# main.net
KiCad netlist of a schematic drawn in EAGLE
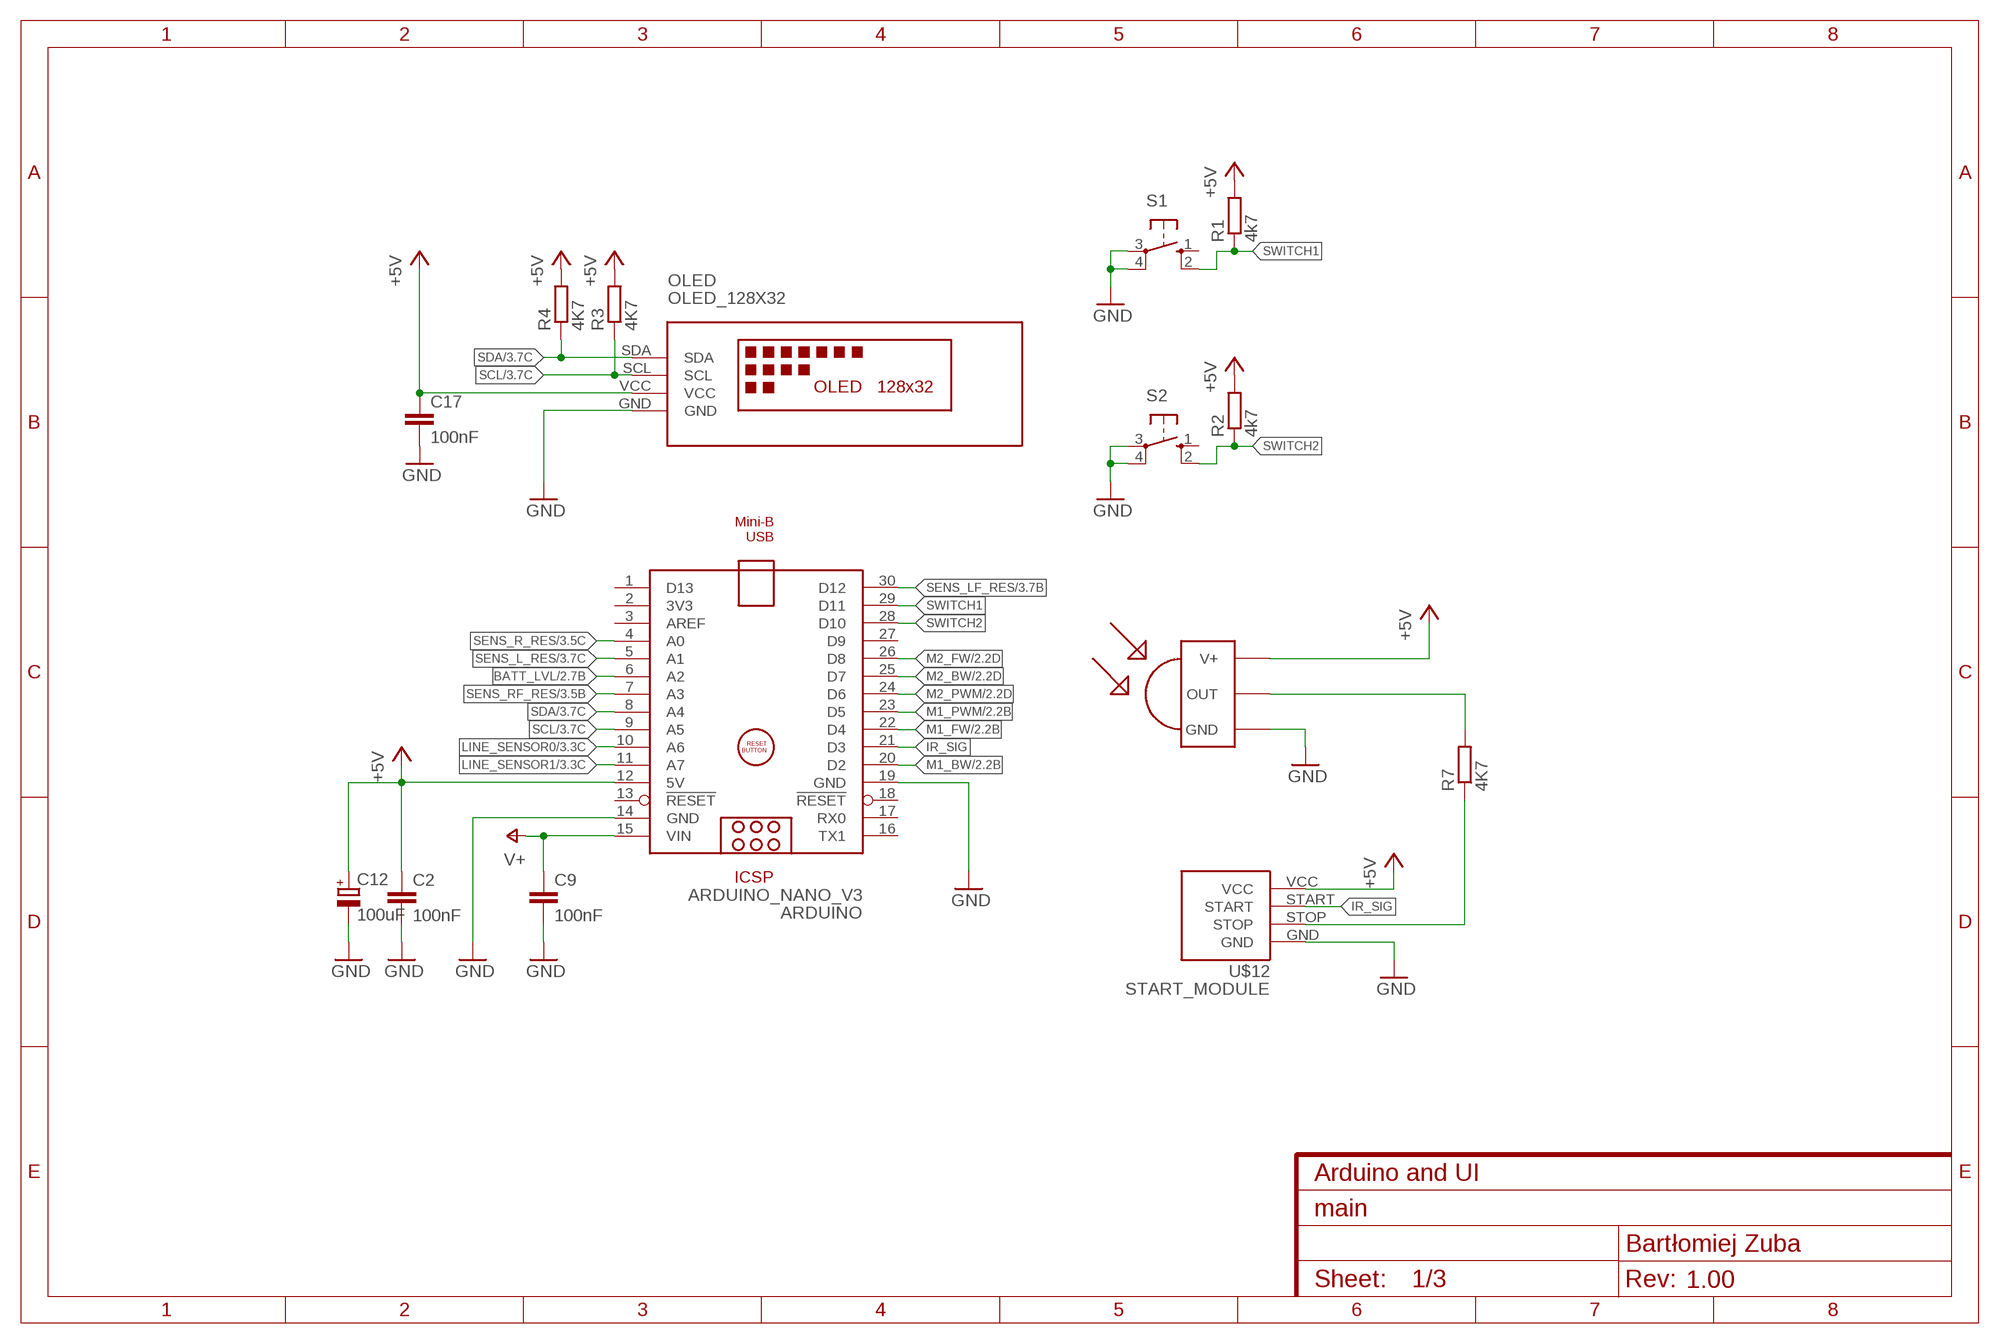
[diagram p0: schematic, sheet 1]
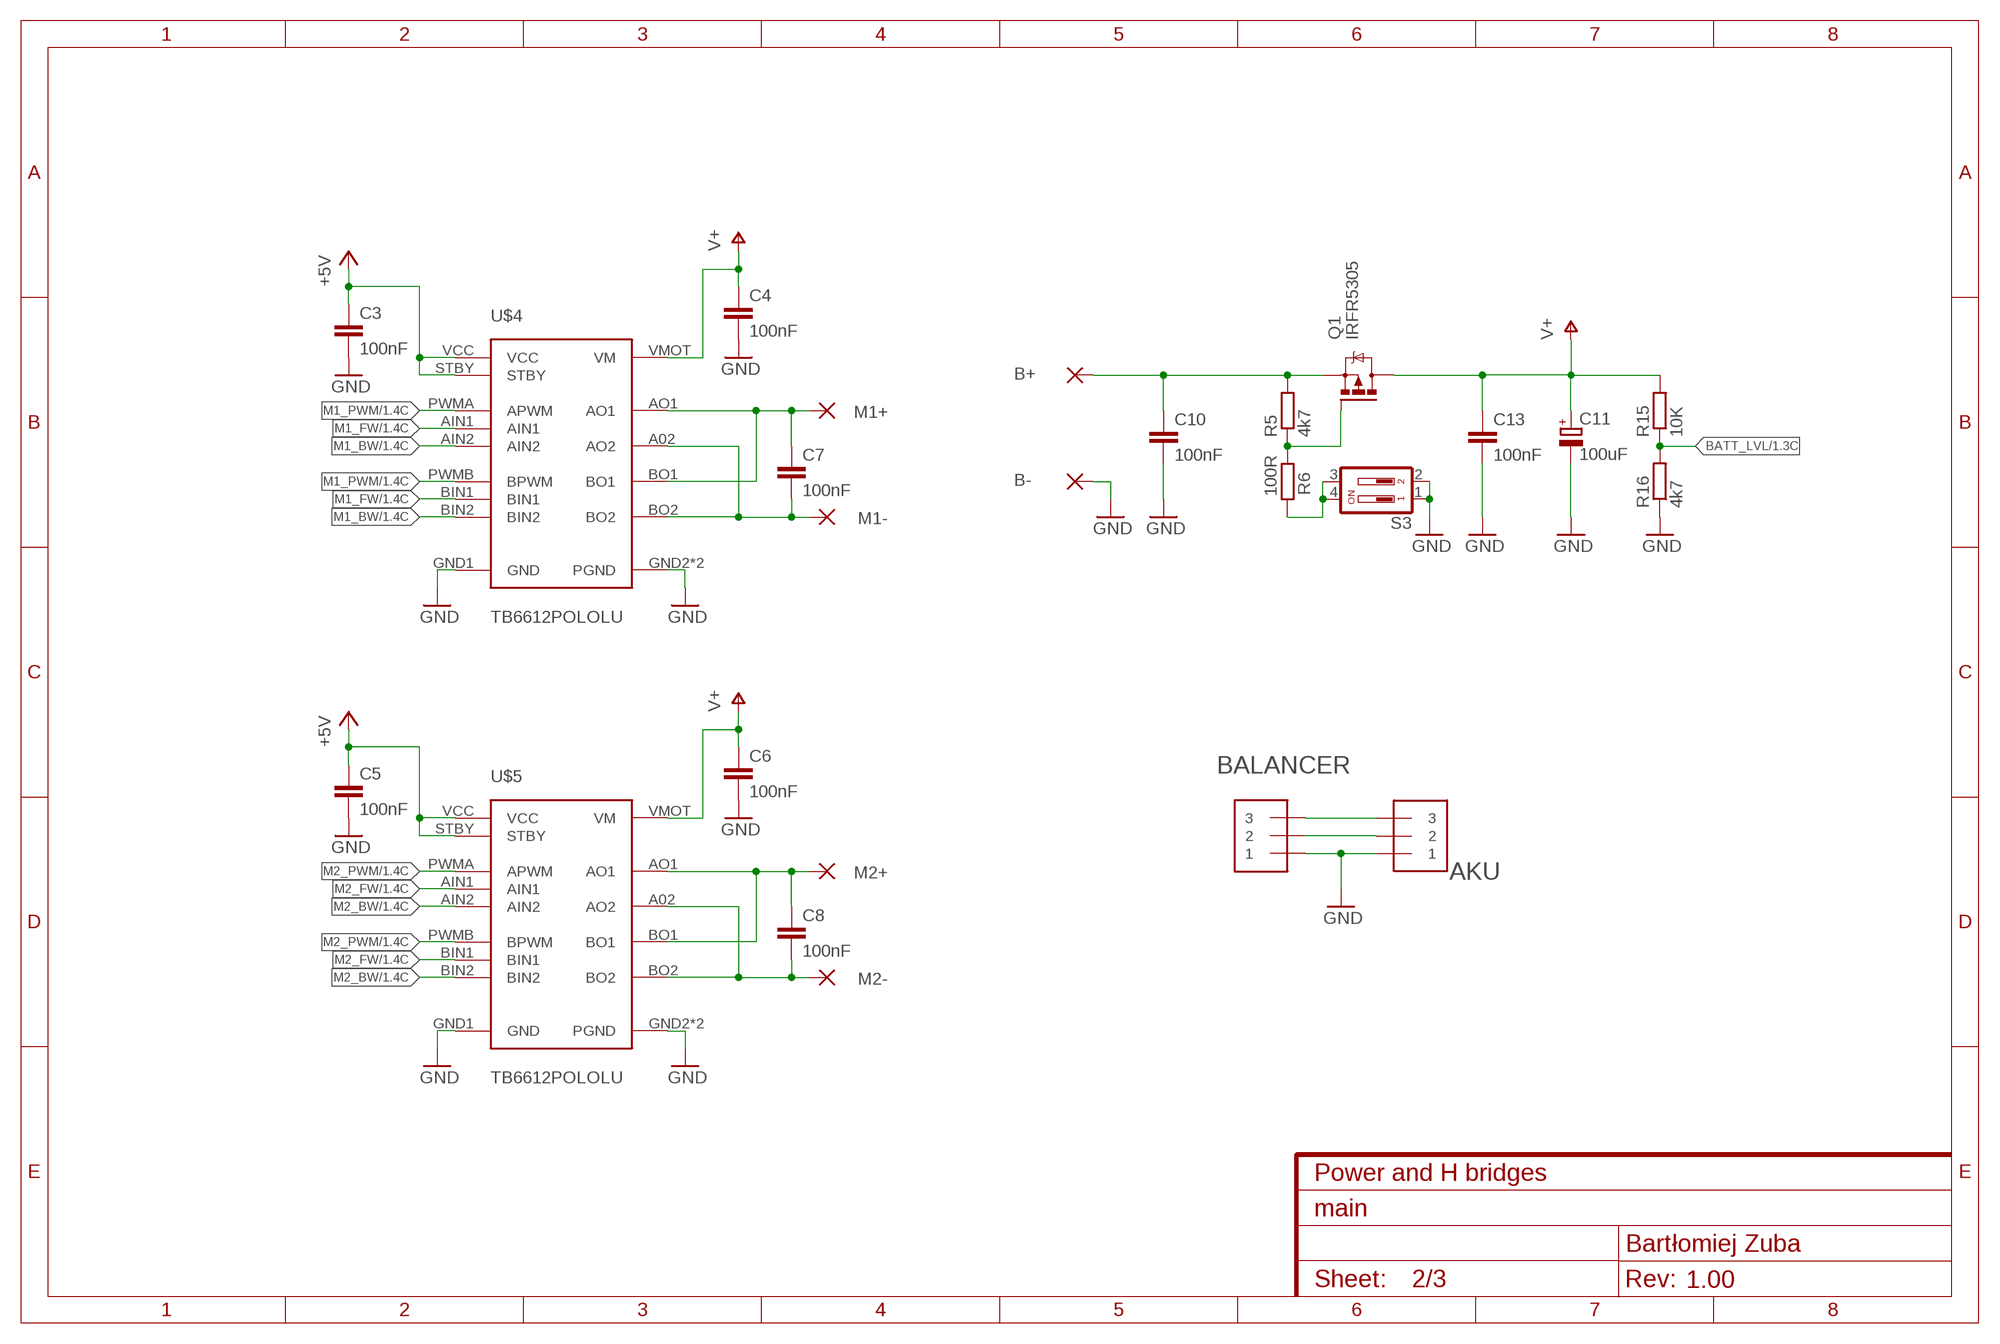
[diagram p1: schematic, sheet 2]
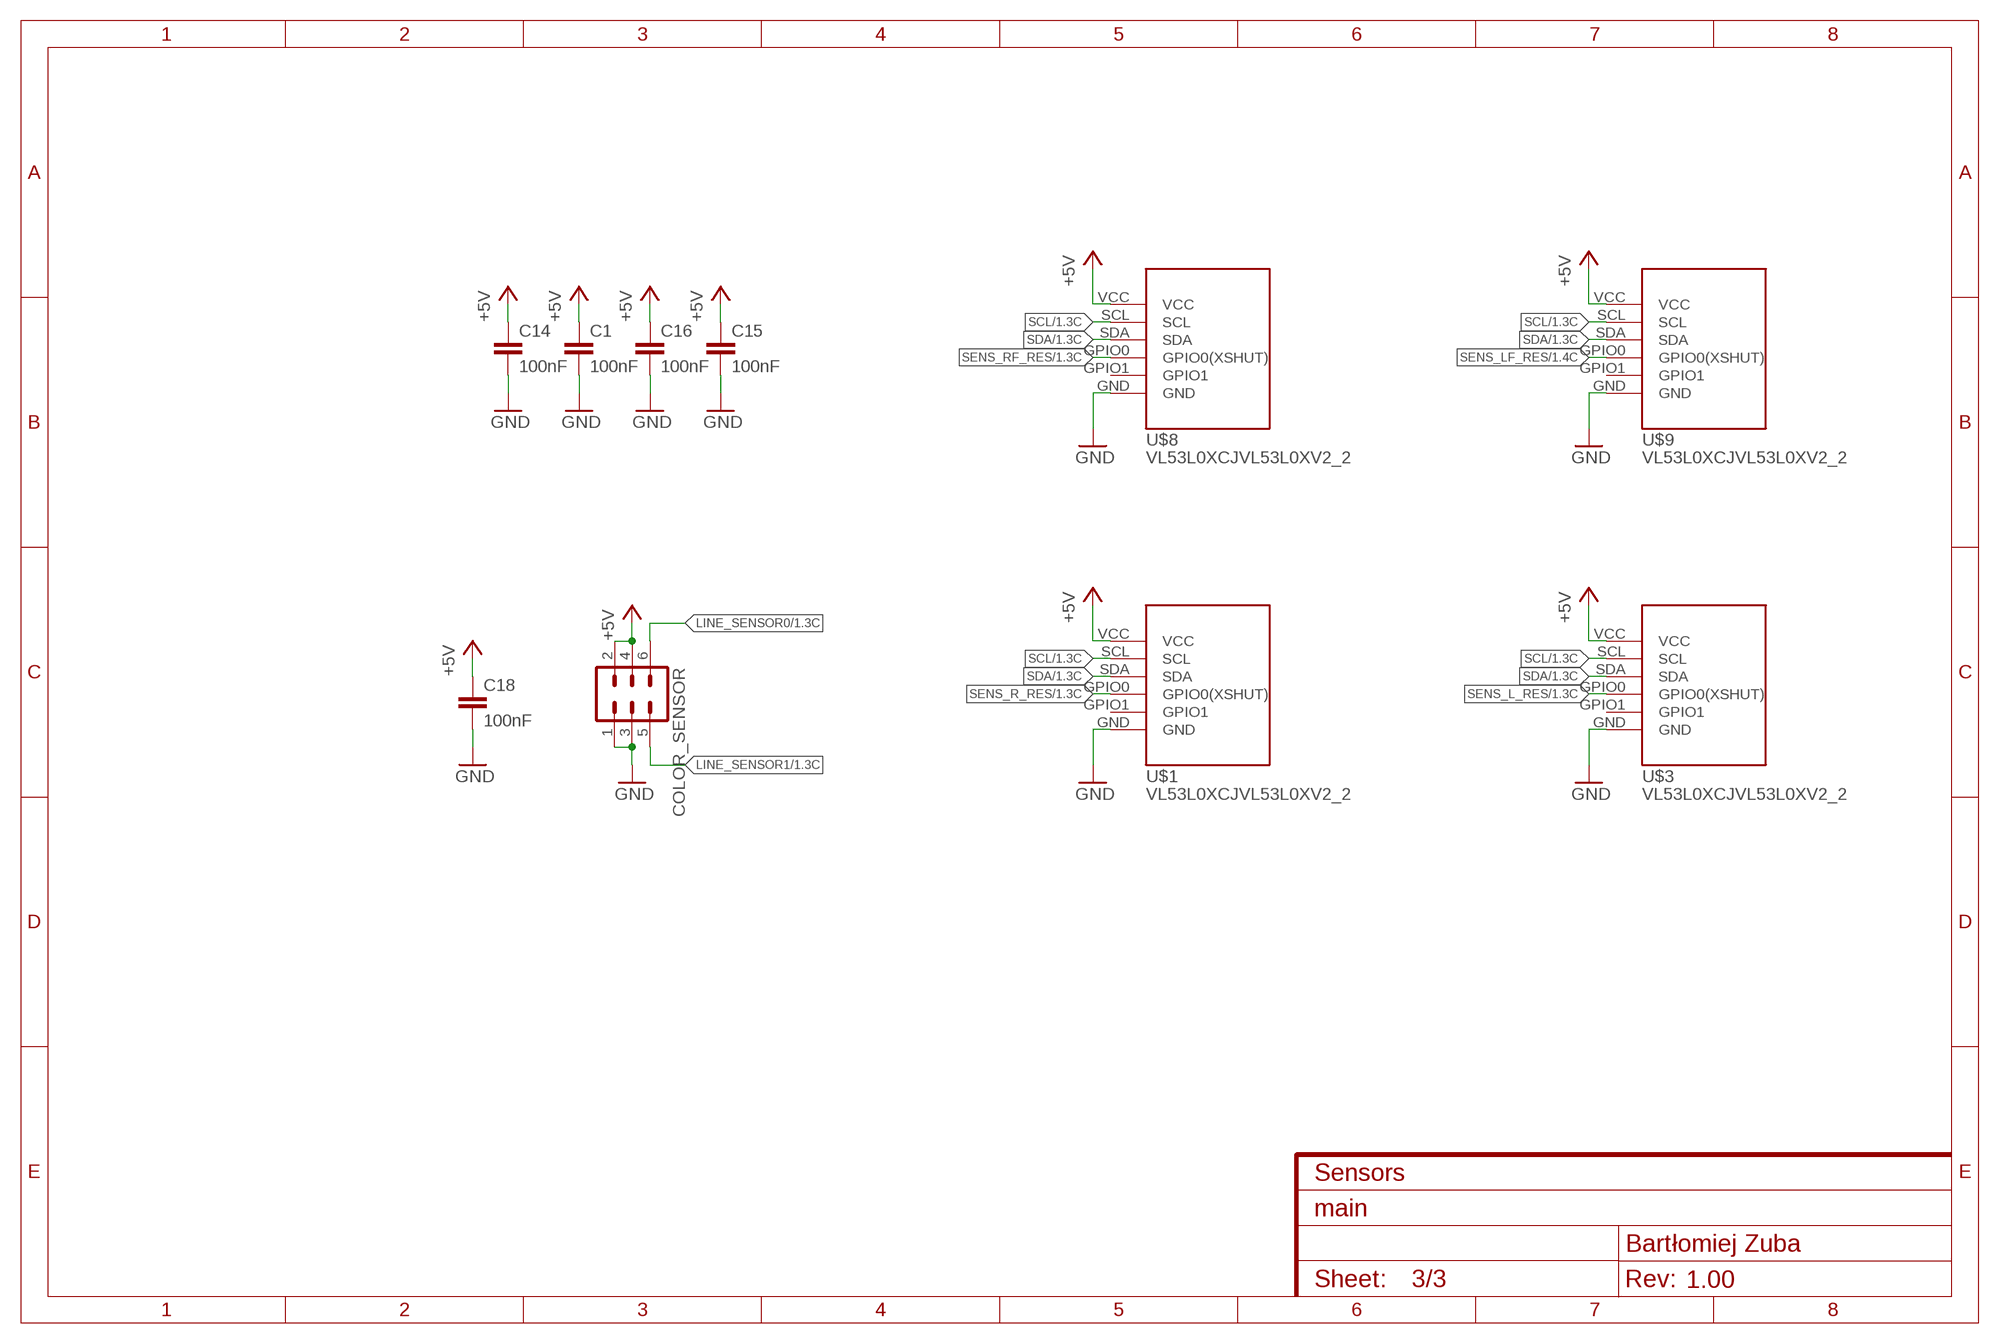
[diagram p2: schematic, sheet 3]

(export (version "E")
  (design (tool "Eeschema 10.0.6"))
  (components
    (comp (ref "AKU")
      (value "JST_ZH_3")
      (footprint "eagle-import:JST_ZH_3")
      (libsource (lib "eagle-import") (part "JST_ZH_3"))
    )
    (comp (ref "B+")
      (value "2,54/1,0")
      (footprint "eagle-import:2,54_1,0")
      (libsource (lib "eagle-import") (part "2,54/1,0"))
    )
    (comp (ref "B-")
      (value "2,54/1,0")
      (footprint "eagle-import:2,54_1,0")
      (libsource (lib "eagle-import") (part "2,54/1,0"))
    )
    (comp (ref "BALANCER")
      (value "JST_ZH_3")
      (footprint "eagle-import:JST_ZH_3")
      (libsource (lib "eagle-import") (part "JST_ZH_3"))
    )
    (comp (ref "C3")
      (value "100nF")
      (footprint "eagle-import:C0805")
      (libsource (lib "eagle-import") (part "C-EUC0805"))
    )
    (comp (ref "C4")
      (value "100nF")
      (footprint "eagle-import:C0805")
      (libsource (lib "eagle-import") (part "C-EUC0805"))
    )
    (comp (ref "C5")
      (value "100nF")
      (footprint "eagle-import:C0805")
      (libsource (lib "eagle-import") (part "C-EUC0805"))
    )
    (comp (ref "C6")
      (value "100nF")
      (footprint "eagle-import:C0805")
      (libsource (lib "eagle-import") (part "C-EUC0805"))
    )
    (comp (ref "C7")
      (value "100nF")
      (footprint "eagle-import:C0805")
      (libsource (lib "eagle-import") (part "C-EUC0805"))
    )
    (comp (ref "C8")
      (value "100nF")
      (footprint "eagle-import:C0805")
      (libsource (lib "eagle-import") (part "C-EUC0805"))
    )
    (comp (ref "C10")
      (value "100nF")
      (footprint "eagle-import:C0805")
      (libsource (lib "eagle-import") (part "C-EUC0805"))
    )
    (comp (ref "C11")
      (value "100uF")
      (footprint "eagle-import:E3,5-8")
      (libsource (lib "eagle-import") (part "CPOL-EUE3.5-8"))
    )
    (comp (ref "C13")
      (value "100nF")
      (footprint "eagle-import:C0805")
      (libsource (lib "eagle-import") (part "C-EUC0805"))
    )
    (comp (ref "M1+")
      (value "2,54/1,0")
      (footprint "eagle-import:2,54_1,0")
      (libsource (lib "eagle-import") (part "2,54/1,0"))
    )
    (comp (ref "M1-")
      (value "2,54/1,0")
      (footprint "eagle-import:2,54_1,0")
      (libsource (lib "eagle-import") (part "2,54/1,0"))
    )
    (comp (ref "M2+")
      (value "2,54/1,0")
      (footprint "eagle-import:2,54_1,0")
      (libsource (lib "eagle-import") (part "2,54/1,0"))
    )
    (comp (ref "M2-")
      (value "2,54/1,0")
      (footprint "eagle-import:2,54_1,0")
      (libsource (lib "eagle-import") (part "2,54/1,0"))
    )
    (comp (ref "Q1")
      (value "IRFR5305")
      (footprint "eagle-import:D-PAK_TO252AA")
      (libsource (lib "eagle-import") (part "IRF?5305R"))
    )
    (comp (ref "R5")
      (value "4k7")
      (footprint "eagle-import:M0805")
      (libsource (lib "eagle-import") (part "R-EU_M0805"))
    )
    (comp (ref "R6")
      (value "100R")
      (footprint "eagle-import:M0805")
      (libsource (lib "eagle-import") (part "R-EU_M0805"))
    )
    (comp (ref "R15")
      (value "10K")
      (footprint "eagle-import:M0805")
      (libsource (lib "eagle-import") (part "R-EU_M0805"))
    )
    (comp (ref "R16")
      (value "4k7")
      (footprint "eagle-import:M0805")
      (libsource (lib "eagle-import") (part "R-EU_M0805"))
    )
    (comp (ref "S3")
      (value "DS02")
      (footprint "eagle-import:DS-02")
      (libsource (lib "eagle-import") (part "DS02"))
    )
    (comp (ref "U$4")
      (value "TB6612POLOLU")
      (footprint "eagle-import:POLOLU")
      (libsource (lib "eagle-import") (part "TB6612POLOLU"))
    )
    (comp (ref "U$5")
      (value "TB6612POLOLU")
      (footprint "eagle-import:POLOLU")
      (libsource (lib "eagle-import") (part "TB6612POLOLU"))
    )
    (comp (ref "ARDUINO")
      (value "ARDUINO_NANO_V3")
      (footprint "eagle-import:ARDUINO_NANO_V3")
      (libsource (lib "eagle-import") (part "ARDUINO_NANO_V3"))
    )
    (comp (ref "C2")
      (value "100nF")
      (footprint "eagle-import:C0805")
      (libsource (lib "eagle-import") (part "C-EUC0805"))
    )
    (comp (ref "C9")
      (value "100nF")
      (footprint "eagle-import:C0805")
      (libsource (lib "eagle-import") (part "C-EUC0805"))
    )
    (comp (ref "C12")
      (value "100uF")
      (footprint "eagle-import:E3,5-8")
      (libsource (lib "eagle-import") (part "CPOL-EUE3.5-8"))
    )
    (comp (ref "C17")
      (value "100nF")
      (footprint "eagle-import:C0805")
      (libsource (lib "eagle-import") (part "C-EUC0805"))
    )
    (comp (ref "OLED")
      (value "OLED_128X32")
      (footprint "eagle-import:OLED")
      (libsource (lib "eagle-import") (part "OLED_128X32"))
    )
    (comp (ref "R1")
      (value "4k7")
      (footprint "eagle-import:M0805")
      (libsource (lib "eagle-import") (part "R-EU_M0805"))
    )
    (comp (ref "R2")
      (value "4k7")
      (footprint "eagle-import:M0805")
      (libsource (lib "eagle-import") (part "R-EU_M0805"))
    )
    (comp (ref "R3")
      (value "4K7")
      (footprint "eagle-import:M0805")
      (libsource (lib "eagle-import") (part "R-EU_M0805"))
    )
    (comp (ref "R4")
      (value "4K7")
      (footprint "eagle-import:M0805")
      (libsource (lib "eagle-import") (part "R-EU_M0805"))
    )
    (comp (ref "R7")
      (value "4K7")
      (footprint "eagle-import:M0805")
      (libsource (lib "eagle-import") (part "R-EU_M0805"))
    )
    (comp (ref "S1")
      (value "10-XX")
      (footprint "eagle-import:B3F-10XX")
      (fields (field (name "MPN") "B3F-1000"))
      (libsource (lib "eagle-import") (part "10-XX"))
    )
    (comp (ref "S2")
      (value "10-XX")
      (footprint "eagle-import:B3F-10XX")
      (fields (field (name "MPN") "B3F-1000"))
      (libsource (lib "eagle-import") (part "10-XX"))
    )
    (comp (ref "U$2")
      (value "TSOP4838")
      (footprint "eagle-import:TSOP")
      (libsource (lib "eagle-import") (part "TSOP4838"))
    )
    (comp (ref "U$12")
      (value "START_MODULE")
      (footprint "eagle-import:START_MODULE")
      (libsource (lib "eagle-import") (part "START_MODULE"))
    )
    (comp (ref "C1")
      (value "100nF")
      (footprint "eagle-import:C0805")
      (libsource (lib "eagle-import") (part "C-EUC0805"))
    )
    (comp (ref "C14")
      (value "100nF")
      (footprint "eagle-import:C0805")
      (libsource (lib "eagle-import") (part "C-EUC0805"))
    )
    (comp (ref "C15")
      (value "100nF")
      (footprint "eagle-import:C0805")
      (libsource (lib "eagle-import") (part "C-EUC0805"))
    )
    (comp (ref "C16")
      (value "100nF")
      (footprint "eagle-import:C0805")
      (libsource (lib "eagle-import") (part "C-EUC0805"))
    )
    (comp (ref "C18")
      (value "100nF")
      (footprint "eagle-import:C0805")
      (libsource (lib "eagle-import") (part "C-EUC0805"))
    )
    (comp (ref "COLOR_SENSOR")
      (value "MA03-2")
      (footprint "eagle-import:MA03-2")
      (libsource (lib "eagle-import") (part "MA03-2"))
    )
    (comp (ref "U$1")
      (value "VL53L0XCJVL53L0XV2_2")
      (footprint "eagle-import:VL53L0X_4")
      (libsource (lib "eagle-import") (part "VL53L0XCJVL53L0XV2_2"))
    )
    (comp (ref "U$3")
      (value "VL53L0XCJVL53L0XV2_2")
      (footprint "eagle-import:VL53L0X_4")
      (libsource (lib "eagle-import") (part "VL53L0XCJVL53L0XV2_2"))
    )
    (comp (ref "U$8")
      (value "VL53L0XCJVL53L0XV2_2")
      (footprint "eagle-import:VL53L0X_4")
      (libsource (lib "eagle-import") (part "VL53L0XCJVL53L0XV2_2"))
    )
    (comp (ref "U$9")
      (value "VL53L0XCJVL53L0XV2_2")
      (footprint "eagle-import:VL53L0X_4")
      (libsource (lib "eagle-import") (part "VL53L0XCJVL53L0XV2_2"))
    )
  )
  (nets
    (net (code "1") (name "+5V") (class "Default")
      (node (ref "ARDUINO") (pin "12") (pinfunction "5V_12") (pintype "power_in"))
      (node (ref "C1") (pin "1") (pinfunction "1_1") (pintype "passive"))
      (node (ref "C12") (pin "+") (pinfunction "+_+") (pintype "passive"))
      (node (ref "C14") (pin "1") (pinfunction "1_1") (pintype "passive"))
      (node (ref "C15") (pin "1") (pinfunction "1_1") (pintype "passive"))
      (node (ref "C16") (pin "1") (pinfunction "1_1") (pintype "passive"))
      (node (ref "C17") (pin "1") (pinfunction "1_1") (pintype "passive"))
      (node (ref "C18") (pin "1") (pinfunction "1_1") (pintype "passive"))
      (node (ref "C2") (pin "1") (pinfunction "1_1") (pintype "passive"))
      (node (ref "C3") (pin "1") (pinfunction "1_1") (pintype "passive"))
      (node (ref "C5") (pin "1") (pinfunction "1_1") (pintype "passive"))
      (node (ref "COLOR_SENSOR") (pin "2") (pinfunction "2_2") (pintype "passive"))
      (node (ref "COLOR_SENSOR") (pin "4") (pinfunction "4_4") (pintype "passive"))
      (node (ref "OLED") (pin "VCC") (pinfunction "VCC_VCC") (pintype "power_in"))
      (node (ref "R1") (pin "2") (pinfunction "2_2") (pintype "passive"))
      (node (ref "R2") (pin "2") (pinfunction "2_2") (pintype "passive"))
      (node (ref "R3") (pin "2") (pinfunction "2_2") (pintype "passive"))
      (node (ref "R4") (pin "2") (pinfunction "2_2") (pintype "passive"))
      (node (ref "U$1") (pin "VCC") (pinfunction "VCC_VCC") (pintype "bidirectional"))
      (node (ref "U$12") (pin "VCC") (pinfunction "VCC_VCC") (pintype "bidirectional"))
      (node (ref "U$2") (pin "VCC") (pinfunction "V+_VCC") (pintype "bidirectional"))
      (node (ref "U$3") (pin "VCC") (pinfunction "VCC_VCC") (pintype "bidirectional"))
      (node (ref "U$4") (pin "STBY") (pinfunction "STBY_STBY") (pintype "bidirectional"))
      (node (ref "U$4") (pin "VCC") (pinfunction "VCC_VCC") (pintype "bidirectional"))
      (node (ref "U$5") (pin "STBY") (pinfunction "STBY_STBY") (pintype "bidirectional"))
      (node (ref "U$5") (pin "VCC") (pinfunction "VCC_VCC") (pintype "bidirectional"))
      (node (ref "U$8") (pin "VCC") (pinfunction "VCC_VCC") (pintype "bidirectional"))
      (node (ref "U$9") (pin "VCC") (pinfunction "VCC_VCC") (pintype "bidirectional"))
    )
    (net (code "2") (name "BATT_LVL") (class "Default")
      (node (ref "ARDUINO") (pin "6") (pinfunction "A2_6") (pintype "bidirectional"))
      (node (ref "R15") (pin "1") (pinfunction "1_1") (pintype "passive"))
      (node (ref "R16") (pin "2") (pinfunction "2_2") (pintype "passive"))
    )
    (net (code "3") (name "GND") (class "Default")
      (node (ref "AKU") (pin "P$1") (pinfunction "1_P$1") (pintype "bidirectional"))
      (node (ref "ARDUINO") (pin "14") (pinfunction "GND_14") (pintype "power_in"))
      (node (ref "ARDUINO") (pin "19") (pinfunction "GND_19") (pintype "power_in"))
      (node (ref "B-") (pin "1") (pinfunction "P_1") (pintype "passive"))
      (node (ref "BALANCER") (pin "P$1") (pinfunction "1_P$1") (pintype "bidirectional"))
      (node (ref "C1") (pin "2") (pinfunction "2_2") (pintype "passive"))
      (node (ref "C10") (pin "2") (pinfunction "2_2") (pintype "passive"))
      (node (ref "C11") (pin "-") (pinfunction "-_-") (pintype "passive"))
      (node (ref "C12") (pin "-") (pinfunction "-_-") (pintype "passive"))
      (node (ref "C13") (pin "2") (pinfunction "2_2") (pintype "passive"))
      (node (ref "C14") (pin "2") (pinfunction "2_2") (pintype "passive"))
      (node (ref "C15") (pin "2") (pinfunction "2_2") (pintype "passive"))
      (node (ref "C16") (pin "2") (pinfunction "2_2") (pintype "passive"))
      (node (ref "C17") (pin "2") (pinfunction "2_2") (pintype "passive"))
      (node (ref "C18") (pin "2") (pinfunction "2_2") (pintype "passive"))
      (node (ref "C2") (pin "2") (pinfunction "2_2") (pintype "passive"))
      (node (ref "C3") (pin "2") (pinfunction "2_2") (pintype "passive"))
      (node (ref "C4") (pin "2") (pinfunction "2_2") (pintype "passive"))
      (node (ref "C5") (pin "2") (pinfunction "2_2") (pintype "passive"))
      (node (ref "C6") (pin "2") (pinfunction "2_2") (pintype "passive"))
      (node (ref "C9") (pin "2") (pinfunction "2_2") (pintype "passive"))
      (node (ref "COLOR_SENSOR") (pin "1") (pinfunction "1_1") (pintype "passive"))
      (node (ref "COLOR_SENSOR") (pin "3") (pinfunction "3_3") (pintype "passive"))
      (node (ref "OLED") (pin "GND") (pinfunction "GND_GND") (pintype "power_in"))
      (node (ref "R16") (pin "1") (pinfunction "1_1") (pintype "passive"))
      (node (ref "S1") (pin "3") (pinfunction "P_3") (pintype "passive"))
      (node (ref "S1") (pin "4") (pinfunction "P1_4") (pintype "passive"))
      (node (ref "S2") (pin "3") (pinfunction "P_3") (pintype "passive"))
      (node (ref "S2") (pin "4") (pinfunction "P1_4") (pintype "passive"))
      (node (ref "S3") (pin "1") (pinfunction "1_1") (pintype "passive"))
      (node (ref "S3") (pin "2") (pinfunction "2_2") (pintype "passive"))
      (node (ref "U$1") (pin "GND") (pinfunction "GND_GND") (pintype "bidirectional"))
      (node (ref "U$12") (pin "GND") (pinfunction "GND_GND") (pintype "bidirectional"))
      (node (ref "U$2") (pin "GND") (pinfunction "GND_GND") (pintype "bidirectional"))
      (node (ref "U$3") (pin "GND") (pinfunction "GND_GND") (pintype "bidirectional"))
      (node (ref "U$4") (pin "GND1") (pinfunction "GND_GND1") (pintype "bidirectional"))
      (node (ref "U$4") (pin "GND2") (pinfunction "PGND_GND2") (pintype "bidirectional"))
      (node (ref "U$4") (pin "GND3") (pinfunction "PGND_GND3") (pintype "bidirectional"))
      (node (ref "U$5") (pin "GND1") (pinfunction "GND_GND1") (pintype "bidirectional"))
      (node (ref "U$5") (pin "GND2") (pinfunction "PGND_GND2") (pintype "bidirectional"))
      (node (ref "U$5") (pin "GND3") (pinfunction "PGND_GND3") (pintype "bidirectional"))
      (node (ref "U$8") (pin "GND") (pinfunction "GND_GND") (pintype "bidirectional"))
      (node (ref "U$9") (pin "GND") (pinfunction "GND_GND") (pintype "bidirectional"))
    )
    (net (code "4") (name "IR_SIG") (class "Default")
      (node (ref "ARDUINO") (pin "21") (pinfunction "D3_21") (pintype "bidirectional"))
      (node (ref "U$12") (pin "START") (pinfunction "START_START") (pintype "bidirectional"))
    )
    (net (code "5") (name "LINE_SENSOR0") (class "Default")
      (node (ref "ARDUINO") (pin "10") (pinfunction "A6_10") (pintype "bidirectional"))
      (node (ref "COLOR_SENSOR") (pin "6") (pinfunction "6_6") (pintype "passive"))
    )
    (net (code "6") (name "LINE_SENSOR1") (class "Default")
      (node (ref "ARDUINO") (pin "11") (pinfunction "A7_11") (pintype "bidirectional"))
      (node (ref "COLOR_SENSOR") (pin "5") (pinfunction "5_5") (pintype "passive"))
    )
    (net (code "7") (name "M1_BW") (class "Default")
      (node (ref "ARDUINO") (pin "20") (pinfunction "D2_20") (pintype "bidirectional"))
      (node (ref "U$4") (pin "AIN2") (pinfunction "AIN2_AIN2") (pintype "bidirectional"))
      (node (ref "U$4") (pin "BIN2") (pinfunction "BIN2_BIN2") (pintype "bidirectional"))
    )
    (net (code "8") (name "M1_FW") (class "Default")
      (node (ref "ARDUINO") (pin "22") (pinfunction "D4_22") (pintype "bidirectional"))
      (node (ref "U$4") (pin "AIN1") (pinfunction "AIN1_AIN1") (pintype "bidirectional"))
      (node (ref "U$4") (pin "BIN1") (pinfunction "BIN1_BIN1") (pintype "bidirectional"))
    )
    (net (code "9") (name "M1_PWM") (class "Default")
      (node (ref "ARDUINO") (pin "23") (pinfunction "D5_23") (pintype "bidirectional"))
      (node (ref "U$4") (pin "PWMA") (pinfunction "APWM_PWMA") (pintype "bidirectional"))
      (node (ref "U$4") (pin "PWMB") (pinfunction "BPWM_PWMB") (pintype "bidirectional"))
    )
    (net (code "10") (name "M2_BW") (class "Default")
      (node (ref "ARDUINO") (pin "25") (pinfunction "D7_25") (pintype "bidirectional"))
      (node (ref "U$5") (pin "AIN2") (pinfunction "AIN2_AIN2") (pintype "bidirectional"))
      (node (ref "U$5") (pin "BIN2") (pinfunction "BIN2_BIN2") (pintype "bidirectional"))
    )
    (net (code "11") (name "M2_FW") (class "Default")
      (node (ref "ARDUINO") (pin "26") (pinfunction "D8_26") (pintype "bidirectional"))
      (node (ref "U$5") (pin "AIN1") (pinfunction "AIN1_AIN1") (pintype "bidirectional"))
      (node (ref "U$5") (pin "BIN1") (pinfunction "BIN1_BIN1") (pintype "bidirectional"))
    )
    (net (code "12") (name "M2_PWM") (class "Default")
      (node (ref "ARDUINO") (pin "24") (pinfunction "D6_24") (pintype "bidirectional"))
      (node (ref "U$5") (pin "PWMA") (pinfunction "APWM_PWMA") (pintype "bidirectional"))
      (node (ref "U$5") (pin "PWMB") (pinfunction "BPWM_PWMB") (pintype "bidirectional"))
    )
    (net (code "13") (name "Net-(AKU-2)") (class "Default")
      (node (ref "AKU") (pin "P$2") (pinfunction "2_P$2") (pintype "bidirectional"))
      (node (ref "BALANCER") (pin "P$2") (pinfunction "2_P$2") (pintype "bidirectional"))
    )
    (net (code "14") (name "Net-(AKU-3)") (class "Default")
      (node (ref "AKU") (pin "P$3") (pinfunction "3_P$3") (pintype "bidirectional"))
      (node (ref "BALANCER") (pin "P$3") (pinfunction "3_P$3") (pintype "bidirectional"))
    )
    (net (code "15") (name "Net-(B+-P)") (class "Default")
      (node (ref "B+") (pin "1") (pinfunction "P_1") (pintype "passive"))
      (node (ref "C10") (pin "1") (pinfunction "1_1") (pintype "passive"))
      (node (ref "Q1") (pin "3") (pinfunction "S_3") (pintype "passive"))
      (node (ref "R5") (pin "2") (pinfunction "2_2") (pintype "passive"))
    )
    (net (code "16") (name "Net-(M1+-P)") (class "Default")
      (node (ref "C7") (pin "1") (pinfunction "1_1") (pintype "passive"))
      (node (ref "M1+") (pin "1") (pinfunction "P_1") (pintype "passive"))
      (node (ref "U$4") (pin "AO1") (pinfunction "AO1_AO1") (pintype "bidirectional"))
      (node (ref "U$4") (pin "BO1") (pinfunction "BO1_BO1") (pintype "bidirectional"))
    )
    (net (code "17") (name "Net-(M1--P)") (class "Default")
      (node (ref "C7") (pin "2") (pinfunction "2_2") (pintype "passive"))
      (node (ref "M1-") (pin "1") (pinfunction "P_1") (pintype "passive"))
      (node (ref "U$4") (pin "A02") (pinfunction "AO2_A02") (pintype "bidirectional"))
      (node (ref "U$4") (pin "BO2") (pinfunction "BO2_BO2") (pintype "bidirectional"))
    )
    (net (code "18") (name "Net-(M2+-P)") (class "Default")
      (node (ref "C8") (pin "1") (pinfunction "1_1") (pintype "passive"))
      (node (ref "M2+") (pin "1") (pinfunction "P_1") (pintype "passive"))
      (node (ref "U$5") (pin "AO1") (pinfunction "AO1_AO1") (pintype "bidirectional"))
      (node (ref "U$5") (pin "BO1") (pinfunction "BO1_BO1") (pintype "bidirectional"))
    )
    (net (code "19") (name "Net-(M2--P)") (class "Default")
      (node (ref "C8") (pin "2") (pinfunction "2_2") (pintype "passive"))
      (node (ref "M2-") (pin "1") (pinfunction "P_1") (pintype "passive"))
      (node (ref "U$5") (pin "A02") (pinfunction "AO2_A02") (pintype "bidirectional"))
      (node (ref "U$5") (pin "BO2") (pinfunction "BO2_BO2") (pintype "bidirectional"))
    )
    (net (code "20") (name "Net-(Q1-G)") (class "Default")
      (node (ref "Q1") (pin "1") (pinfunction "G_1") (pintype "passive"))
      (node (ref "R5") (pin "1") (pinfunction "1_1") (pintype "passive"))
      (node (ref "R6") (pin "1") (pinfunction "1_1") (pintype "passive"))
    )
    (net (code "21") (name "Net-(R6-Pad2)") (class "Default")
      (node (ref "R6") (pin "2") (pinfunction "2_2") (pintype "passive"))
      (node (ref "S3") (pin "3") (pinfunction "3_3") (pintype "passive"))
      (node (ref "S3") (pin "4") (pinfunction "4_4") (pintype "passive"))
    )
    (net (code "22") (name "Net-(R7-Pad1)") (class "Default")
      (node (ref "R7") (pin "1") (pinfunction "1_1") (pintype "passive"))
      (node (ref "U$12") (pin "STOP") (pinfunction "STOP_STOP") (pintype "bidirectional"))
    )
    (net (code "23") (name "Net-(R7-Pad2)") (class "Default")
      (node (ref "R7") (pin "2") (pinfunction "2_2") (pintype "passive"))
      (node (ref "U$2") (pin "OUT") (pinfunction "OUT_OUT") (pintype "bidirectional"))
    )
    (net (code "24") (name "SCL") (class "Default")
      (node (ref "ARDUINO") (pin "9") (pinfunction "A5_9") (pintype "bidirectional"))
      (node (ref "OLED") (pin "SCL") (pinfunction "SCL_SCL") (pintype "bidirectional"))
      (node (ref "R3") (pin "1") (pinfunction "1_1") (pintype "passive"))
      (node (ref "U$1") (pin "SCL") (pinfunction "SCL_SCL") (pintype "bidirectional"))
      (node (ref "U$3") (pin "SCL") (pinfunction "SCL_SCL") (pintype "bidirectional"))
      (node (ref "U$8") (pin "SCL") (pinfunction "SCL_SCL") (pintype "bidirectional"))
      (node (ref "U$9") (pin "SCL") (pinfunction "SCL_SCL") (pintype "bidirectional"))
    )
    (net (code "25") (name "SDA") (class "Default")
      (node (ref "ARDUINO") (pin "8") (pinfunction "A4_8") (pintype "bidirectional"))
      (node (ref "OLED") (pin "SDA") (pinfunction "SDA_SDA") (pintype "bidirectional"))
      (node (ref "R4") (pin "1") (pinfunction "1_1") (pintype "passive"))
      (node (ref "U$1") (pin "SDA") (pinfunction "SDA_SDA") (pintype "bidirectional"))
      (node (ref "U$3") (pin "SDA") (pinfunction "SDA_SDA") (pintype "bidirectional"))
      (node (ref "U$8") (pin "SDA") (pinfunction "SDA_SDA") (pintype "bidirectional"))
      (node (ref "U$9") (pin "SDA") (pinfunction "SDA_SDA") (pintype "bidirectional"))
    )
    (net (code "26") (name "SENS_LF_RES") (class "Default")
      (node (ref "ARDUINO") (pin "30") (pinfunction "D12_30") (pintype "bidirectional"))
      (node (ref "U$9") (pin "GPIO0") (pinfunction "GPIO0(XSHUT)_GPIO0") (pintype "bidirectional"))
    )
    (net (code "27") (name "SENS_L_RES") (class "Default")
      (node (ref "ARDUINO") (pin "5") (pinfunction "A1_5") (pintype "bidirectional"))
      (node (ref "U$3") (pin "GPIO0") (pinfunction "GPIO0(XSHUT)_GPIO0") (pintype "bidirectional"))
    )
    (net (code "28") (name "SENS_RF_RES") (class "Default")
      (node (ref "ARDUINO") (pin "7") (pinfunction "A3_7") (pintype "bidirectional"))
      (node (ref "U$8") (pin "GPIO0") (pinfunction "GPIO0(XSHUT)_GPIO0") (pintype "bidirectional"))
    )
    (net (code "29") (name "SENS_R_RES") (class "Default")
      (node (ref "ARDUINO") (pin "4") (pinfunction "A0_4") (pintype "bidirectional"))
      (node (ref "U$1") (pin "GPIO0") (pinfunction "GPIO0(XSHUT)_GPIO0") (pintype "bidirectional"))
    )
    (net (code "30") (name "SWITCH1") (class "Default")
      (node (ref "ARDUINO") (pin "29") (pinfunction "D11_29") (pintype "bidirectional"))
      (node (ref "R1") (pin "1") (pinfunction "1_1") (pintype "passive"))
      (node (ref "S1") (pin "2") (pinfunction "S1_2") (pintype "passive"))
    )
    (net (code "31") (name "SWITCH2") (class "Default")
      (node (ref "ARDUINO") (pin "28") (pinfunction "D10_28") (pintype "bidirectional"))
      (node (ref "R2") (pin "1") (pinfunction "1_1") (pintype "passive"))
      (node (ref "S2") (pin "2") (pinfunction "S1_2") (pintype "passive"))
    )
    (net (code "32") (name "V+") (class "Default")
      (node (ref "ARDUINO") (pin "15") (pinfunction "VIN_15") (pintype "power_in"))
      (node (ref "C11") (pin "+") (pinfunction "+_+") (pintype "passive"))
      (node (ref "C13") (pin "1") (pinfunction "1_1") (pintype "passive"))
      (node (ref "C4") (pin "1") (pinfunction "1_1") (pintype "passive"))
      (node (ref "C6") (pin "1") (pinfunction "1_1") (pintype "passive"))
      (node (ref "C9") (pin "1") (pinfunction "1_1") (pintype "passive"))
      (node (ref "Q1") (pin "4") (pinfunction "D_4") (pintype "passive"))
      (node (ref "R15") (pin "2") (pinfunction "2_2") (pintype "passive"))
      (node (ref "U$4") (pin "VMOT") (pinfunction "VM_VMOT") (pintype "bidirectional"))
      (node (ref "U$5") (pin "VMOT") (pinfunction "VM_VMOT") (pintype "bidirectional"))
    )
    (net (code "33") (name "unconnected-(ARDUINO-3V3-Pad2)") (class "Default")
      (node (ref "ARDUINO") (pin "2") (pinfunction "3V3_2") (pintype "output"))
    )
    (net (code "34") (name "unconnected-(ARDUINO-AREF-Pad3)") (class "Default")
      (node (ref "ARDUINO") (pin "3") (pinfunction "AREF_3") (pintype "input"))
    )
    (net (code "35") (name "unconnected-(ARDUINO-D9-Pad27)") (class "Default")
      (node (ref "ARDUINO") (pin "27") (pinfunction "D9_27") (pintype "bidirectional"))
    )
    (net (code "36") (name "unconnected-(ARDUINO-D13-Pad1)") (class "Default")
      (node (ref "ARDUINO") (pin "1") (pinfunction "D13_1") (pintype "bidirectional"))
    )
    (net (code "37") (name "unconnected-(ARDUINO-RX0-Pad17)") (class "Default")
      (node (ref "ARDUINO") (pin "17") (pinfunction "RX0_17") (pintype "bidirectional"))
    )
    (net (code "38") (name "unconnected-(ARDUINO-TX1-Pad16)") (class "Default")
      (node (ref "ARDUINO") (pin "16") (pinfunction "TX1_16") (pintype "bidirectional"))
    )
    (net (code "39") (name "unconnected-(ARDUINO-~{RESET}-Pad13)") (class "Default")
      (node (ref "ARDUINO") (pin "13") (pinfunction "~{RESET}_13") (pintype "input"))
    )
    (net (code "40") (name "unconnected-(ARDUINO-~{RESET}-Pad18)") (class "Default")
      (node (ref "ARDUINO") (pin "18") (pinfunction "~{RESET}_18") (pintype "input"))
    )
    (net (code "41") (name "unconnected-(S1-S-Pad1)") (class "Default")
      (node (ref "S1") (pin "1") (pinfunction "S_1") (pintype "passive"))
    )
    (net (code "42") (name "unconnected-(S2-S-Pad1)") (class "Default")
      (node (ref "S2") (pin "1") (pinfunction "S_1") (pintype "passive"))
    )
    (net (code "43") (name "unconnected-(U$1-PadGPIO1)") (class "Default")
      (node (ref "U$1") (pin "GPIO1") (pinfunction "GPIO1_GPIO1") (pintype "bidirectional"))
    )
    (net (code "44") (name "unconnected-(U$3-PadGPIO1)") (class "Default")
      (node (ref "U$3") (pin "GPIO1") (pinfunction "GPIO1_GPIO1") (pintype "bidirectional"))
    )
    (net (code "45") (name "unconnected-(U$8-PadGPIO1)") (class "Default")
      (node (ref "U$8") (pin "GPIO1") (pinfunction "GPIO1_GPIO1") (pintype "bidirectional"))
    )
    (net (code "46") (name "unconnected-(U$9-PadGPIO1)") (class "Default")
      (node (ref "U$9") (pin "GPIO1") (pinfunction "GPIO1_GPIO1") (pintype "bidirectional"))
    )
  )
)
